# SUPERHOOP.net
KiCad netlist of a schematic drawn in EAGLE
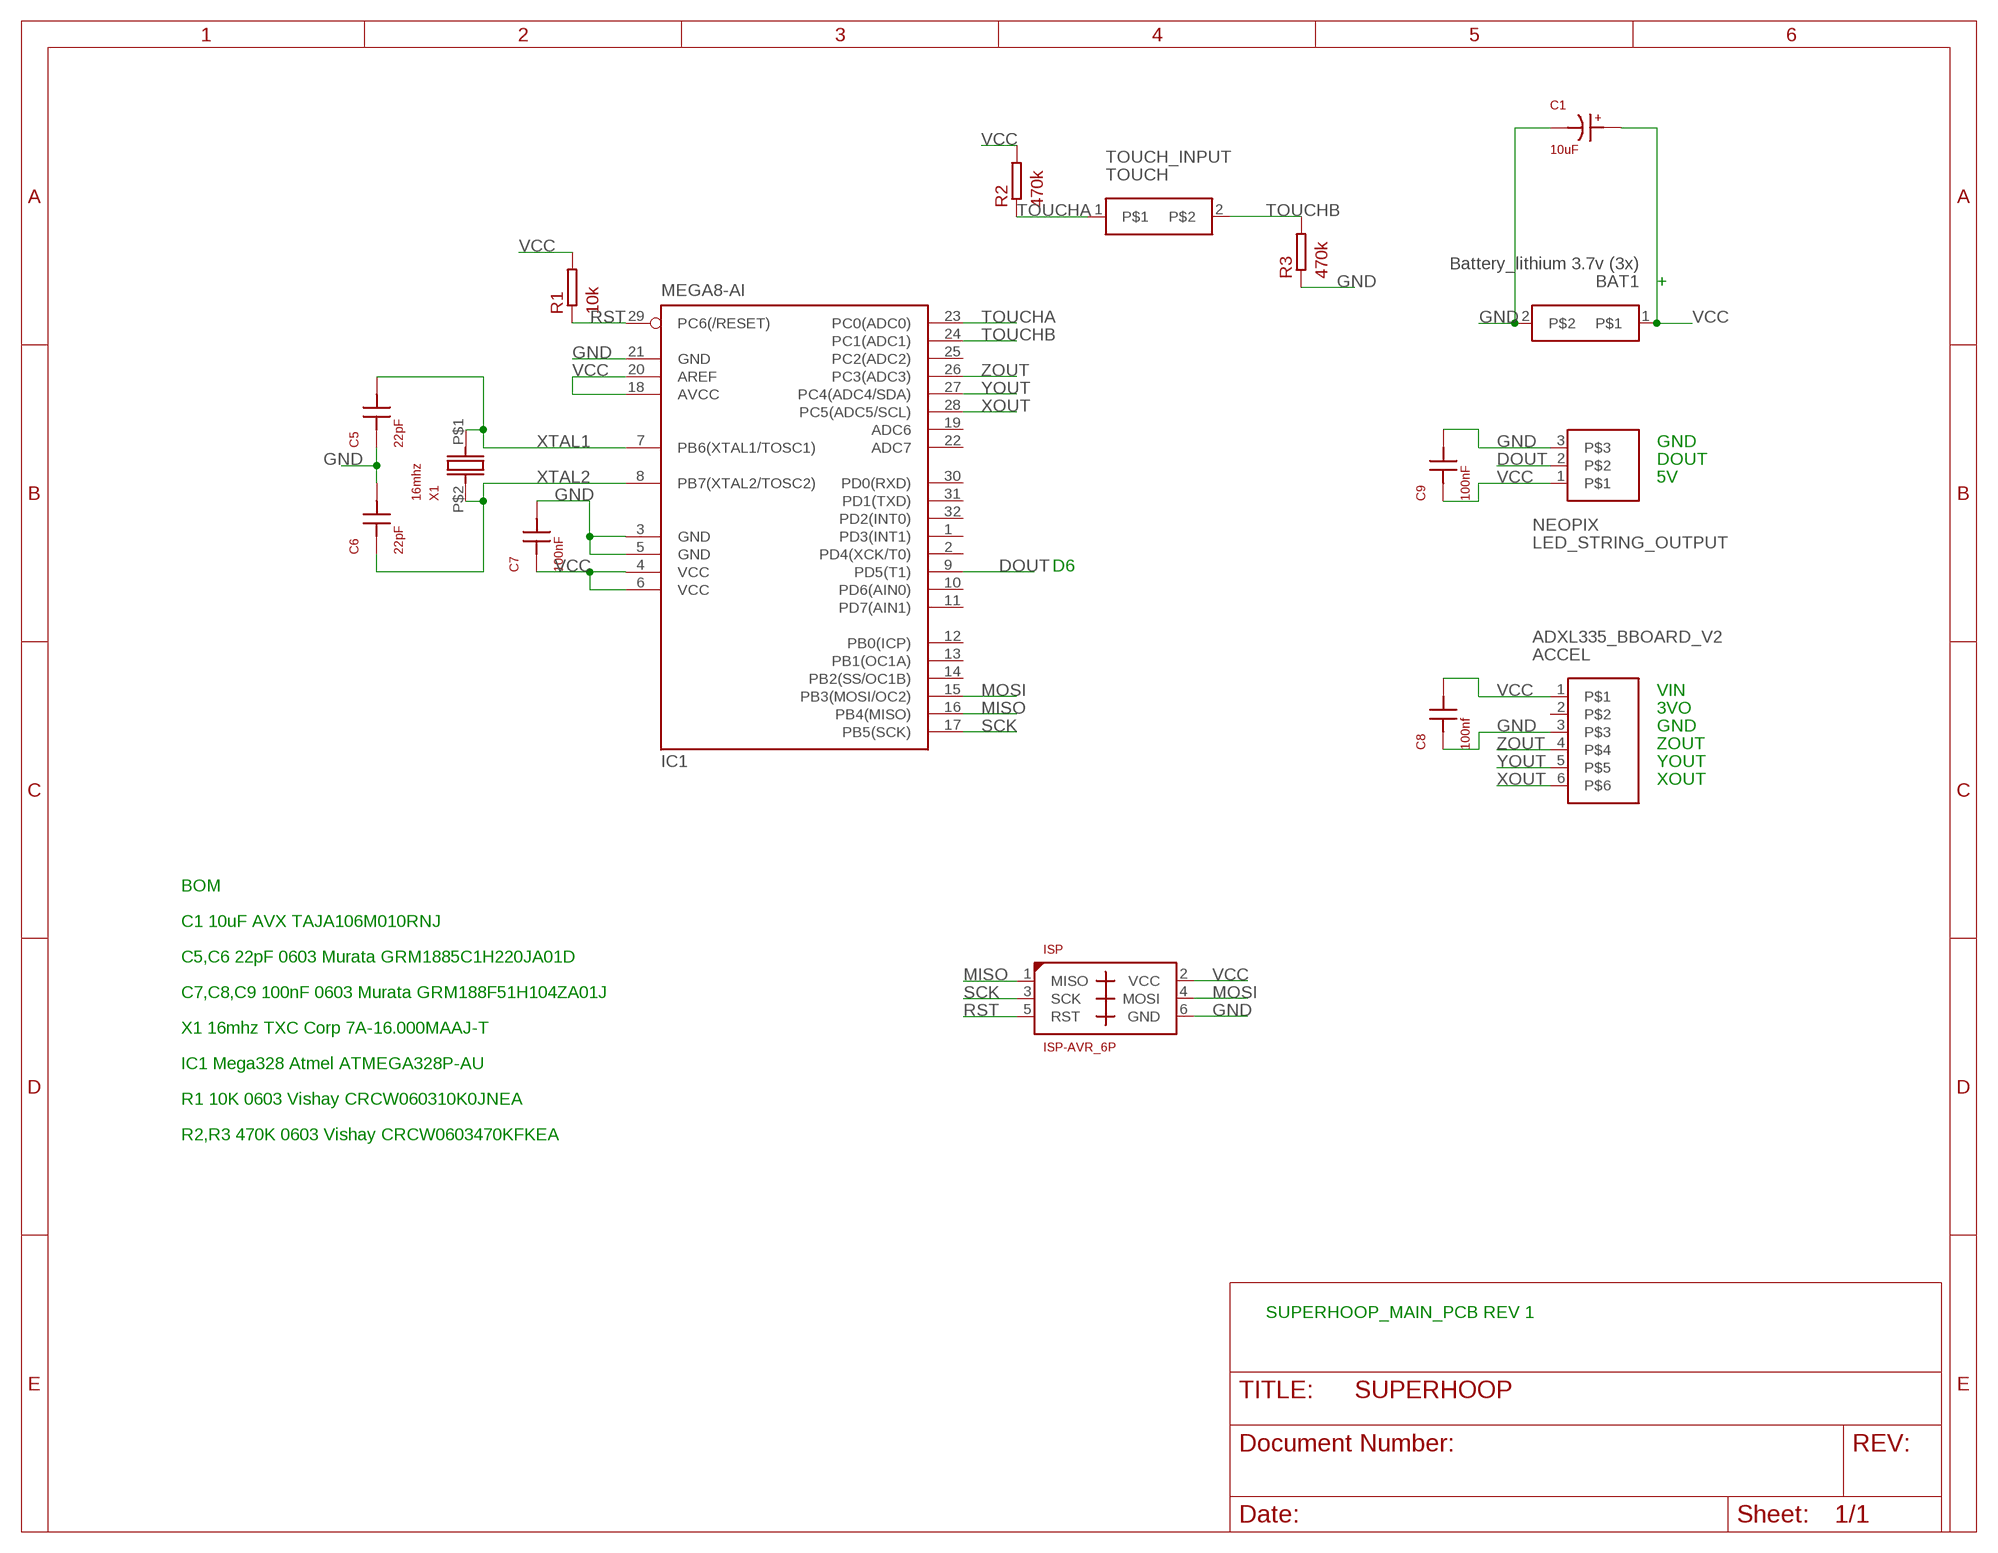
[diagram p0: schematic, sheet 1]

(export (version "E")
  (design (tool "Eeschema 10.0.6"))
  (components
    (comp (ref "ACCEL")
      (value "ADXL335_BBOARD_V2")
      (footprint "eagle-import:HEADER_6X1_2.54")
      (libsource (lib "eagle-import") (part "HEADER_6X1_2.54"))
    )
    (comp (ref "BAT1")
      (value "Battery_lithium 3.7v (3x)")
      (footprint "eagle-import:HEADER_2X1_2.54")
      (libsource (lib "eagle-import") (part "HEADER_2X1_2.54"))
    )
    (comp (ref "C1")
      (value "10uF")
      (footprint "eagle-import:CAP_POL_1206")
      (libsource (lib "eagle-import") (part "CAP_POL_SMD_1206"))
    )
    (comp (ref "C5")
      (value "22pF")
      (footprint "eagle-import:SMD_0603")
      (libsource (lib "eagle-import") (part "CAP_NP_0603"))
    )
    (comp (ref "C6")
      (value "22pF")
      (footprint "eagle-import:SMD_0603")
      (libsource (lib "eagle-import") (part "CAP_NP_0603"))
    )
    (comp (ref "C7")
      (value "100nF")
      (footprint "eagle-import:SMD_0603")
      (libsource (lib "eagle-import") (part "CAP_NP_0603"))
    )
    (comp (ref "C8")
      (value "100nf")
      (footprint "eagle-import:SMD_0603")
      (libsource (lib "eagle-import") (part "CAP_NP_0603"))
    )
    (comp (ref "C9")
      (value "100nF")
      (footprint "eagle-import:SMD_0603")
      (libsource (lib "eagle-import") (part "CAP_NP_0603"))
    )
    (comp (ref "IC1")
      (value "MEGA8-AI")
      (footprint "eagle-import:TQFP32-08")
      (fields (field (name "MPN") "ATMEGA8-16AU"))
      (libsource (lib "eagle-import") (part "MEGA8-AI"))
    )
    (comp (ref "ISP")
      (value "ISP-AVR_6P")
      (footprint "eagle-import:HEADER_3X2_2.54")
      (libsource (lib "eagle-import") (part "ISP-AVR_6P"))
    )
    (comp (ref "NEOPIX")
      (value "LED_STRING_OUTPUT")
      (footprint "eagle-import:HEADER_3X1_2.54")
      (libsource (lib "eagle-import") (part "HEADER_3X1"))
    )
    (comp (ref "R1")
      (value "10k")
      (footprint "eagle-import:SMD_0603")
      (libsource (lib "eagle-import") (part "RESISTOR_0603"))
    )
    (comp (ref "R2")
      (value "470k")
      (footprint "eagle-import:SMD_0603")
      (libsource (lib "eagle-import") (part "RESISTOR_0603"))
    )
    (comp (ref "R3")
      (value "470k")
      (footprint "eagle-import:SMD_0603")
      (libsource (lib "eagle-import") (part "RESISTOR_0603"))
    )
    (comp (ref "TOUCH")
      (value "TOUCH_INPUT")
      (footprint "eagle-import:HEADER_2X1_2.54")
      (libsource (lib "eagle-import") (part "HEADER_2X1_2.54"))
    )
    (comp (ref "X1")
      (value "16mhz")
      (footprint "eagle-import:CRYSTAL_5.0X3.2")
      (libsource (lib "eagle-import") (part "CRYSTAL_SMD_5.0X3.2"))
    )
  )
  (nets
    (net (code "1") (name "/DOUT") (class "Default")
      (node (ref "IC1") (pin "9") (pinfunction "PD5(T1)_9") (pintype "bidirectional"))
      (node (ref "NEOPIX") (pin "2") (pinfunction "P$2_2") (pintype "bidirectional"))
    )
    (net (code "2") (name "/GND") (class "Default")
      (node (ref "ACCEL") (pin "3") (pinfunction "P$3_3") (pintype "bidirectional"))
      (node (ref "BAT1") (pin "2") (pinfunction "P$2_2") (pintype "bidirectional"))
      (node (ref "C1") (pin "N") (pinfunction "N_N") (pintype "passive"))
      (node (ref "C5") (pin "P$1") (pinfunction "P$1_P$1") (pintype "passive"))
      (node (ref "C6") (pin "P$2") (pinfunction "P$2_P$2") (pintype "passive"))
      (node (ref "C7") (pin "P$2") (pinfunction "P$2_P$2") (pintype "passive"))
      (node (ref "C8") (pin "P$1") (pinfunction "P$1_P$1") (pintype "passive"))
      (node (ref "C9") (pin "P$2") (pinfunction "P$2_P$2") (pintype "passive"))
      (node (ref "IC1") (pin "21") (pinfunction "GND_21") (pintype "power_in"))
      (node (ref "IC1") (pin "3") (pinfunction "GND_3") (pintype "power_in"))
      (node (ref "IC1") (pin "5") (pinfunction "GND_5") (pintype "power_in"))
      (node (ref "ISP") (pin "6") (pinfunction "GND_6") (pintype "power_in"))
      (node (ref "NEOPIX") (pin "3") (pinfunction "P$3_3") (pintype "bidirectional"))
      (node (ref "R3") (pin "P$1") (pinfunction "P$1_P$1") (pintype "passive"))
    )
    (net (code "3") (name "/MISO") (class "Default")
      (node (ref "IC1") (pin "16") (pinfunction "PB4(MISO)_16") (pintype "bidirectional"))
      (node (ref "ISP") (pin "1") (pinfunction "MISO_1") (pintype "bidirectional"))
    )
    (net (code "4") (name "/MOSI") (class "Default")
      (node (ref "IC1") (pin "15") (pinfunction "PB3(MOSI/OC2)_15") (pintype "bidirectional"))
      (node (ref "ISP") (pin "4") (pinfunction "MOSI_4") (pintype "bidirectional"))
    )
    (net (code "5") (name "/RST") (class "Default")
      (node (ref "IC1") (pin "29") (pinfunction "PC6(/RESET)_29") (pintype "bidirectional"))
      (node (ref "ISP") (pin "5") (pinfunction "RST_5") (pintype "bidirectional"))
      (node (ref "R1") (pin "P$1") (pinfunction "P$1_P$1") (pintype "passive"))
    )
    (net (code "6") (name "/SCK") (class "Default")
      (node (ref "IC1") (pin "17") (pinfunction "PB5(SCK)_17") (pintype "bidirectional"))
      (node (ref "ISP") (pin "3") (pinfunction "SCK_3") (pintype "bidirectional"))
    )
    (net (code "7") (name "/TOUCHA") (class "Default")
      (node (ref "IC1") (pin "23") (pinfunction "PC0(ADC0)_23") (pintype "bidirectional"))
      (node (ref "R2") (pin "P$1") (pinfunction "P$1_P$1") (pintype "passive"))
      (node (ref "TOUCH") (pin "1") (pinfunction "P$1_1") (pintype "bidirectional"))
    )
    (net (code "8") (name "/TOUCHB") (class "Default")
      (node (ref "IC1") (pin "24") (pinfunction "PC1(ADC1)_24") (pintype "bidirectional"))
      (node (ref "R3") (pin "P$2") (pinfunction "P$2_P$2") (pintype "passive"))
      (node (ref "TOUCH") (pin "2") (pinfunction "P$2_2") (pintype "bidirectional"))
    )
    (net (code "9") (name "/VCC") (class "Default")
      (node (ref "ACCEL") (pin "1") (pinfunction "P$1_1") (pintype "bidirectional"))
      (node (ref "BAT1") (pin "1") (pinfunction "P$1_1") (pintype "bidirectional"))
      (node (ref "C1") (pin "P") (pinfunction "P_P") (pintype "passive"))
      (node (ref "C7") (pin "P$1") (pinfunction "P$1_P$1") (pintype "passive"))
      (node (ref "C8") (pin "P$2") (pinfunction "P$2_P$2") (pintype "passive"))
      (node (ref "C9") (pin "P$1") (pinfunction "P$1_P$1") (pintype "passive"))
      (node (ref "IC1") (pin "18") (pinfunction "AVCC_18") (pintype "power_in"))
      (node (ref "IC1") (pin "20") (pinfunction "AREF_20") (pintype "passive"))
      (node (ref "IC1") (pin "4") (pinfunction "VCC_4") (pintype "power_in"))
      (node (ref "IC1") (pin "6") (pinfunction "VCC_6") (pintype "power_in"))
      (node (ref "ISP") (pin "2") (pinfunction "VCC_2") (pintype "power_in"))
      (node (ref "NEOPIX") (pin "1") (pinfunction "P$1_1") (pintype "bidirectional"))
      (node (ref "R1") (pin "P$2") (pinfunction "P$2_P$2") (pintype "passive"))
      (node (ref "R2") (pin "P$2") (pinfunction "P$2_P$2") (pintype "passive"))
    )
    (net (code "10") (name "/XOUT") (class "Default")
      (node (ref "ACCEL") (pin "6") (pinfunction "P$6_6") (pintype "bidirectional"))
      (node (ref "IC1") (pin "28") (pinfunction "PC5(ADC5/SCL)_28") (pintype "bidirectional"))
    )
    (net (code "11") (name "/XTAL1") (class "Default")
      (node (ref "C5") (pin "P$2") (pinfunction "P$2_P$2") (pintype "passive"))
      (node (ref "IC1") (pin "7") (pinfunction "PB6(XTAL1/TOSC1)_7") (pintype "bidirectional"))
      (node (ref "X1") (pin "P$1") (pinfunction "P$1_P$1") (pintype "passive"))
    )
    (net (code "12") (name "/XTAL2") (class "Default")
      (node (ref "C6") (pin "P$1") (pinfunction "P$1_P$1") (pintype "passive"))
      (node (ref "IC1") (pin "8") (pinfunction "PB7(XTAL2/TOSC2)_8") (pintype "bidirectional"))
      (node (ref "X1") (pin "P$2") (pinfunction "P$2_P$2") (pintype "passive"))
    )
    (net (code "13") (name "/YOUT") (class "Default")
      (node (ref "ACCEL") (pin "5") (pinfunction "P$5_5") (pintype "bidirectional"))
      (node (ref "IC1") (pin "27") (pinfunction "PC4(ADC4/SDA)_27") (pintype "bidirectional"))
    )
    (net (code "14") (name "/ZOUT") (class "Default")
      (node (ref "ACCEL") (pin "4") (pinfunction "P$4_4") (pintype "bidirectional"))
      (node (ref "IC1") (pin "26") (pinfunction "PC3(ADC3)_26") (pintype "bidirectional"))
    )
    (net (code "15") (name "unconnected-(ACCEL-P$2-Pad2)") (class "Default")
      (node (ref "ACCEL") (pin "2") (pinfunction "P$2_2") (pintype "bidirectional"))
    )
    (net (code "16") (name "unconnected-(IC1-ADC6-Pad19)") (class "Default")
      (node (ref "IC1") (pin "19") (pinfunction "ADC6_19") (pintype "bidirectional"))
    )
    (net (code "17") (name "unconnected-(IC1-ADC7-Pad22)") (class "Default")
      (node (ref "IC1") (pin "22") (pinfunction "ADC7_22") (pintype "bidirectional"))
    )
    (net (code "18") (name "unconnected-(IC1-PB0(ICP)-Pad12)") (class "Default")
      (node (ref "IC1") (pin "12") (pinfunction "PB0(ICP)_12") (pintype "bidirectional"))
    )
    (net (code "19") (name "unconnected-(IC1-PB1(OC1A)-Pad13)") (class "Default")
      (node (ref "IC1") (pin "13") (pinfunction "PB1(OC1A)_13") (pintype "bidirectional"))
    )
    (net (code "20") (name "unconnected-(IC1-PB2(SS{slash}OC1B)-Pad14)") (class "Default")
      (node (ref "IC1") (pin "14") (pinfunction "PB2(SS/OC1B)_14") (pintype "bidirectional"))
    )
    (net (code "21") (name "unconnected-(IC1-PC2(ADC2)-Pad25)") (class "Default")
      (node (ref "IC1") (pin "25") (pinfunction "PC2(ADC2)_25") (pintype "bidirectional"))
    )
    (net (code "22") (name "unconnected-(IC1-PD0(RXD)-Pad30)") (class "Default")
      (node (ref "IC1") (pin "30") (pinfunction "PD0(RXD)_30") (pintype "bidirectional"))
    )
    (net (code "23") (name "unconnected-(IC1-PD1(TXD)-Pad31)") (class "Default")
      (node (ref "IC1") (pin "31") (pinfunction "PD1(TXD)_31") (pintype "bidirectional"))
    )
    (net (code "24") (name "unconnected-(IC1-PD2(INT0)-Pad32)") (class "Default")
      (node (ref "IC1") (pin "32") (pinfunction "PD2(INT0)_32") (pintype "bidirectional"))
    )
    (net (code "25") (name "unconnected-(IC1-PD3(INT1)-Pad1)") (class "Default")
      (node (ref "IC1") (pin "1") (pinfunction "PD3(INT1)_1") (pintype "bidirectional"))
    )
    (net (code "26") (name "unconnected-(IC1-PD4(XCK{slash}T0)-Pad2)") (class "Default")
      (node (ref "IC1") (pin "2") (pinfunction "PD4(XCK/T0)_2") (pintype "bidirectional"))
    )
    (net (code "27") (name "unconnected-(IC1-PD6(AIN0)-Pad10)") (class "Default")
      (node (ref "IC1") (pin "10") (pinfunction "PD6(AIN0)_10") (pintype "bidirectional"))
    )
    (net (code "28") (name "unconnected-(IC1-PD7(AIN1)-Pad11)") (class "Default")
      (node (ref "IC1") (pin "11") (pinfunction "PD7(AIN1)_11") (pintype "bidirectional"))
    )
  )
)
